# CON_USBA_RA_UPRIGHT.net
KiCad netlist of a schematic drawn in Altium Designer
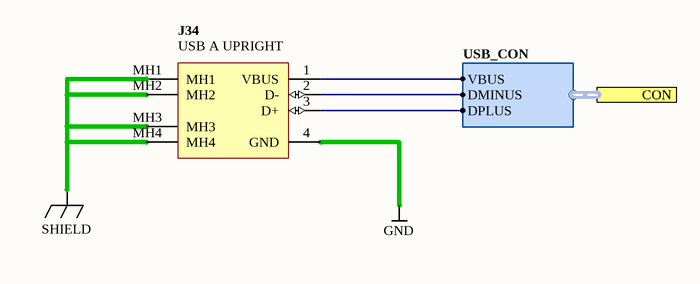
[diagram p0: CON_USBA_RA_UPRIGHT.SchDoc]

(export (version "E")
  (design (tool "Eeschema 10.0.6"))
  (components
    (comp (ref "J34")
      (value "USB A UPRIGHT")
      (footprint "482040001")
      (description "CONNECTOR USB RT ANG RECEPT TYPE A")
      (libsource (lib "AltiumDesignLibrary") (part "USB-UPRIGHT"))
    )
  )
  (nets
    (net (code "2") (name "/DMINUS") (class "Default")
      (node (ref "J34") (pin "2") (pinfunction "D-_2") (pintype "bidirectional"))
    )
    (net (code "3") (name "/DPLUS") (class "Default")
      (node (ref "J34") (pin "3") (pinfunction "D+_3") (pintype "bidirectional"))
    )
    (net (code "4") (name "/VBUS") (class "Default")
      (node (ref "J34") (pin "1") (pinfunction "VBUS_1") (pintype "power_in"))
    )
    (net (code "6") (name "GND") (class "Default")
      (node (ref "J34") (pin "4") (pinfunction "GND_4") (pintype "power_in"))
    )
    (net (code "7") (name "SHIELD") (class "Default")
      (node (ref "J34") (pin "MH1") (pinfunction "MH1_MH1") (pintype "passive"))
      (node (ref "J34") (pin "MH2") (pinfunction "MH2_MH2") (pintype "passive"))
      (node (ref "J34") (pin "MH3") (pinfunction "MH3_MH3") (pintype "passive"))
      (node (ref "J34") (pin "MH4") (pinfunction "MH4_MH4") (pintype "passive"))
    )
  )
)
